# Alimentation_2V.net
KiCad netlist of a schematic drawn in Altium Designer
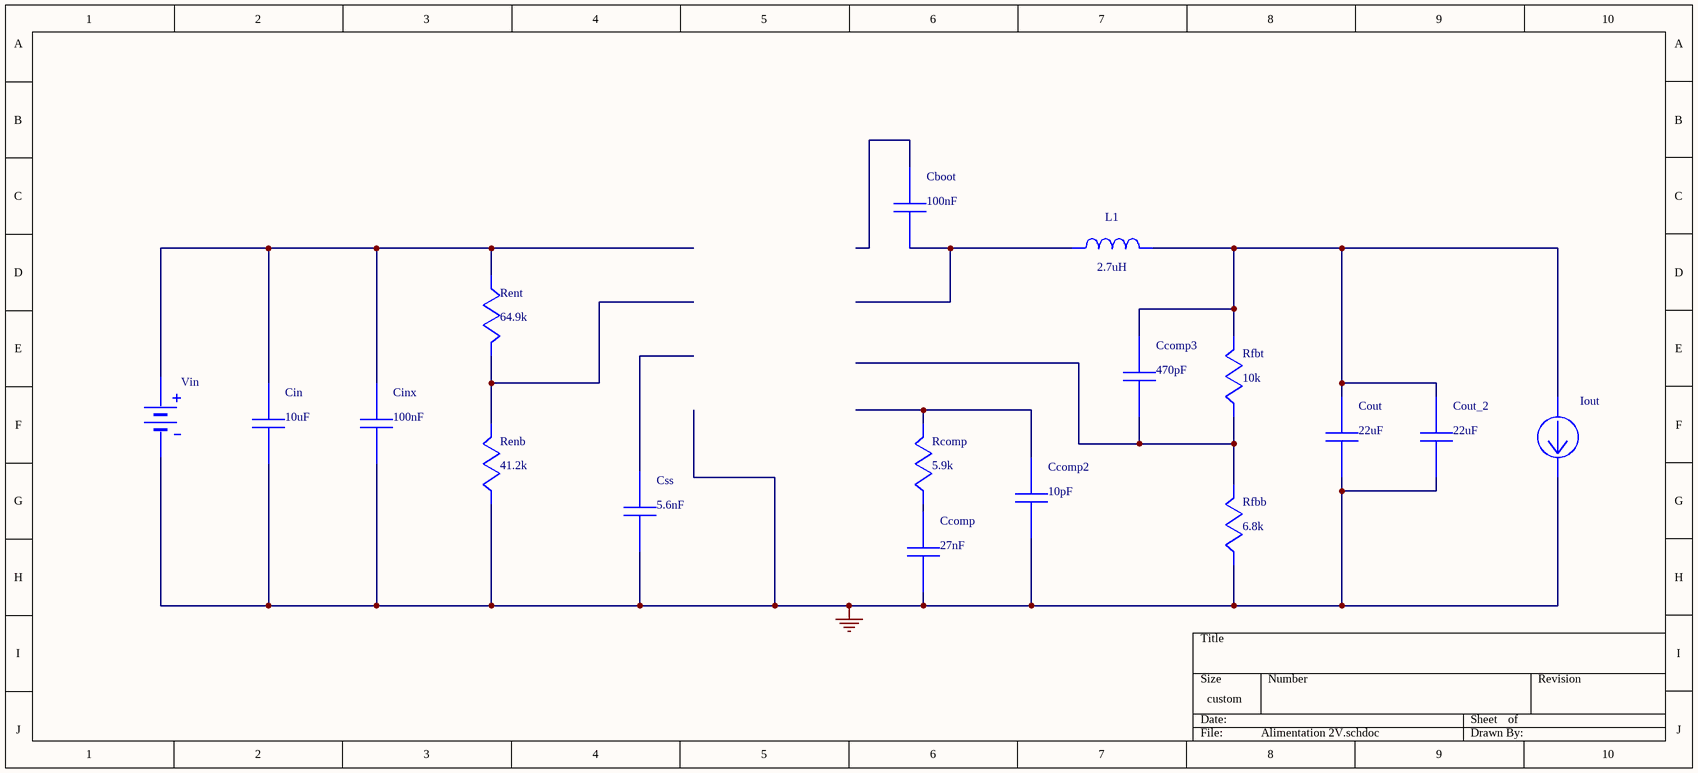
[diagram p0: Alimentation 2V.schdoc]

(export (version "E")
  (design (tool "Eeschema 10.0.6"))
  (components
    (comp (ref "Cboot")
      (value "100nF")
      (description "08053C104JAZ2A")
      (libsource (lib "TI WEBENCH") (part "Cboot"))
    )
    (comp (ref "Ccomp")
      (value "27nF")
      (description "C1812C273J5GACTU")
      (libsource (lib "TI WEBENCH") (part "Ccomp"))
    )
    (comp (ref "Ccomp2")
      (value "10pF")
      (description "CL21C100JBANNNC")
      (libsource (lib "TI WEBENCH") (part "Ccomp2"))
    )
    (comp (ref "Ccomp3")
      (value "470pF")
      (description "CL21C471KBANNNC")
      (libsource (lib "TI WEBENCH") (part "Ccomp3"))
    )
    (comp (ref "Cin")
      (value "10uF")
      (description "C0805C106K8PACTU")
      (libsource (lib "TI WEBENCH") (part "Cin"))
    )
    (comp (ref "Cinx")
      (value "100nF")
      (description "GRM155R70J104KA0")
      (fields (field (name "MANUFACTURER PART NUMBER") "GRM155R70J104KA01D"))
      (libsource (lib "TI WEBENCH") (part "Cinx"))
    )
    (comp (ref "Cout")
      (value "22uF")
      (description "GRM188R60J226MEA")
      (fields (field (name "MANUFACTURER PART NUMBER") "GRM188R60J226MEA0D"))
      (libsource (lib "TI WEBENCH") (part "Cout"))
    )
    (comp (ref "Cout_2")
      (value "22uF")
      (description "GRM188R60J226MEA")
      (fields (field (name "MANUFACTURER PART NUMBER") "GRM188R60J226MEA0D"))
      (libsource (lib "TI WEBENCH") (part "Cout_2"))
    )
    (comp (ref "Css")
      (value "5.6nF")
      (description "CGA4C2C0G1H562J0")
      (fields (field (name "MANUFACTURER PART NUMBER") "CGA4C2C0G1H562J060AA"))
      (libsource (lib "TI WEBENCH") (part "Css"))
    )
    (comp (ref "Iout") (value "WB_CURRENT_LOAD") (libsource (lib "TI WEBENCH") (part "Iout")))
    (comp (ref "L1")
      (value "2.7uH")
      (description "1255AY-2R7N=P3")
      (libsource (lib "TI WEBENCH") (part "L1"))
    )
    (comp (ref "Rcomp")
      (value "5.9k")
      (description "CRCW04025K90FKED")
      (libsource (lib "TI WEBENCH") (part "Rcomp"))
    )
    (comp (ref "Renb")
      (value "41.2k")
      (description "CRCW060341K2FKEA")
      (libsource (lib "TI WEBENCH") (part "Renb"))
    )
    (comp (ref "Rent")
      (value "64.9k")
      (description "CRCW080564K9FKEA")
      (libsource (lib "TI WEBENCH") (part "Rent"))
    )
    (comp (ref "Rfbb")
      (value "6.8k")
      (description "RC0603FR-076K8L")
      (libsource (lib "TI WEBENCH") (part "Rfbb"))
    )
    (comp (ref "Rfbt")
      (value "10k")
      (description "RC0201FR-0710KL")
      (libsource (lib "TI WEBENCH") (part "Rfbt"))
    )
    (comp (ref "Vin") (value "WB_BATTERY") (libsource (lib "TI WEBENCH") (part "Vin")))
  )
  (nets
    (net (code "1") (name "0") (class "Default")
      (node (ref "Ccomp") (pin "2") (pinfunction "2_2") (pintype "passive"))
      (node (ref "Ccomp2") (pin "2") (pinfunction "2_2") (pintype "passive"))
      (node (ref "Cin") (pin "2") (pinfunction "2_2") (pintype "passive"))
      (node (ref "Cinx") (pin "2") (pinfunction "2_2") (pintype "passive"))
      (node (ref "Cout") (pin "2") (pinfunction "2_2") (pintype "passive"))
      (node (ref "Cout_2") (pin "2") (pinfunction "2_2") (pintype "passive"))
      (node (ref "Css") (pin "2") (pinfunction "2_2") (pintype "passive"))
      (node (ref "Iout") (pin "2") (pinfunction "-_2") (pintype "passive"))
      (node (ref "Renb") (pin "2") (pinfunction "2_2") (pintype "passive"))
      (node (ref "Rfbb") (pin "2") (pinfunction "2_2") (pintype "passive"))
      (node (ref "Vin") (pin "2") (pinfunction "-_2") (pintype "passive"))
    )
    (net (code "2") (name "Net-(Cboot-Pad1)") (class "Default")
      (node (ref "Cboot") (pin "1") (pinfunction "1_1") (pintype "passive"))
      (node (ref "L1") (pin "1") (pinfunction "1_1") (pintype "passive"))
    )
    (net (code "3") (name "Net-(Ccomp-Pad1)") (class "Default")
      (node (ref "Ccomp") (pin "1") (pinfunction "1_1") (pintype "passive"))
      (node (ref "Rcomp") (pin "2") (pinfunction "2_2") (pintype "passive"))
    )
    (net (code "4") (name "Net-(Ccomp2-Pad1)") (class "Default")
      (node (ref "Ccomp2") (pin "1") (pinfunction "1_1") (pintype "passive"))
      (node (ref "Rcomp") (pin "1") (pinfunction "1_1") (pintype "passive"))
    )
    (net (code "5") (name "Net-(Ccomp3-Pad1)") (class "Default")
      (node (ref "Ccomp3") (pin "1") (pinfunction "1_1") (pintype "passive"))
      (node (ref "Rfbb") (pin "1") (pinfunction "1_1") (pintype "passive"))
      (node (ref "Rfbt") (pin "2") (pinfunction "2_2") (pintype "passive"))
    )
    (net (code "6") (name "Net-(Iout-+)") (class "Default")
      (node (ref "Ccomp3") (pin "2") (pinfunction "2_2") (pintype "passive"))
      (node (ref "Cout") (pin "1") (pinfunction "1_1") (pintype "passive"))
      (node (ref "Cout_2") (pin "1") (pinfunction "1_1") (pintype "passive"))
      (node (ref "Iout") (pin "1") (pinfunction "+_1") (pintype "passive"))
      (node (ref "L1") (pin "2") (pinfunction "2_2") (pintype "passive"))
      (node (ref "Rfbt") (pin "1") (pinfunction "1_1") (pintype "passive"))
    )
    (net (code "7") (name "Net-(Renb-Pad1)") (class "Default")
      (node (ref "Renb") (pin "1") (pinfunction "1_1") (pintype "passive"))
      (node (ref "Rent") (pin "1") (pinfunction "1_1") (pintype "passive"))
    )
    (net (code "8") (name "Net-(Vin-+)") (class "Default")
      (node (ref "Cin") (pin "1") (pinfunction "1_1") (pintype "passive"))
      (node (ref "Cinx") (pin "1") (pinfunction "1_1") (pintype "passive"))
      (node (ref "Rent") (pin "2") (pinfunction "2_2") (pintype "passive"))
      (node (ref "Vin") (pin "1") (pinfunction "+_1") (pintype "passive"))
    )
    (net (code "9") (name "unconnected-(Cboot-Pad2)") (class "Default")
      (node (ref "Cboot") (pin "2") (pinfunction "2_2") (pintype "passive"))
    )
    (net (code "10") (name "unconnected-(Css-Pad1)") (class "Default")
      (node (ref "Css") (pin "1") (pinfunction "1_1") (pintype "passive"))
    )
  )
)
